# Sheet1.net
KiCad netlist of a schematic drawn in Altium Designer
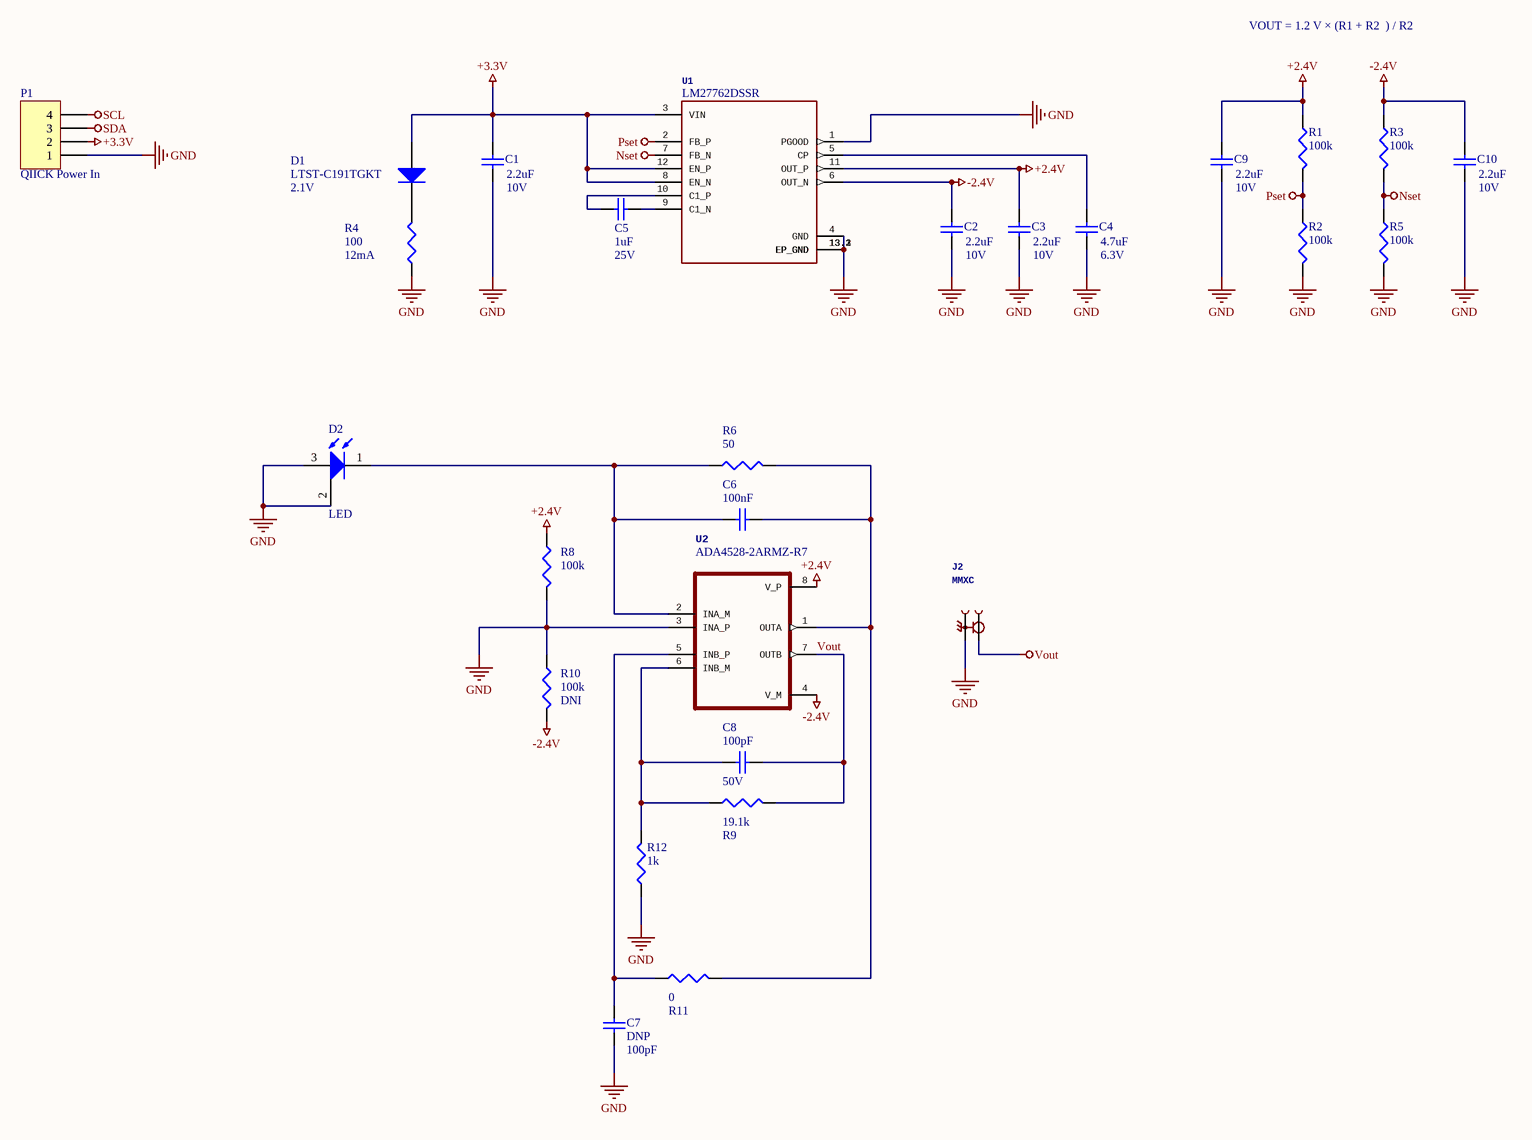
[diagram p0: Sheet1.SchDoc]

(export (version "E")
  (design (tool "Eeschema 10.0.6"))
  (components
    (comp (ref "C1")
      (value "10V")
      (footprint "0402")
      (description "2.2 µF ±20% 16V Ceramic Capacitor X6S 0402 (1005 Metric)")
      (fields (field (name "ALTIUM_VALUE") "2.2uF") (field (name "MANUFACTURER PART #") "CC0402MRX6S7BB225"))
      (libsource (lib "Miscellaneous Devices") (part "Cap"))
    )
    (comp (ref "C2")
      (value "10V")
      (footprint "0402")
      (description "2.2 µF ±20% 16V Ceramic Capacitor X6S 0402 (1005 Metric)")
      (fields (field (name "ALTIUM_VALUE") "2.2uF") (field (name "MANUFACTURER PART #") "CC0402MRX6S7BB225"))
      (libsource (lib "Miscellaneous Devices") (part "Cap"))
    )
    (comp (ref "C3")
      (value "10V")
      (footprint "0402")
      (description "2.2 µF ±20% 16V Ceramic Capacitor X6S 0402 (1005 Metric)")
      (fields (field (name "ALTIUM_VALUE") "2.2uF") (field (name "MANUFACTURER PART #") "CC0402MRX6S7BB225"))
      (libsource (lib "Miscellaneous Devices") (part "Cap"))
    )
    (comp (ref "C4")
      (value "6.3V")
      (footprint "0402")
      (description "4.7 µF ±20% 6.3V Ceramic Capacitor X6S 0402 (1005 Metric)")
      (fields (field (name "ALTIUM_VALUE") "4.7uF") (field (name "MANUFACTURER PART #") "CC0402MRX6S5BB475"))
      (libsource (lib "Miscellaneous Devices") (part "Cap"))
    )
    (comp (ref "C5")
      (value "25V")
      (footprint "0402")
      (description "1 µF ±10% 25V Ceramic Capacitor X5R 0402 (1005 Metric)")
      (fields (field (name "ALTIUM_VALUE") "1uF") (field (name "MANUFACTURER PART #") "CC0402KPX5R8BB105"))
      (libsource (lib "Miscellaneous Devices") (part "Cap"))
    )
    (comp (ref "C6")
      (value "100nF")
      (footprint "1608[0603]")
      (description "0.1 µF -20%, +80% 50V Ceramic Capacitor Y5V (F) 0603 (1608 Metric)")
      (fields (field (name "MANUFACTURER") "YAGEO") (field (name "MANUFACTURER PART #") "CC0603ZPY5V9BB104"))
      (libsource (lib "Miscellaneous Devices") (part "Cap Semi"))
    )
    (comp (ref "C7")
      (value "DNP")
      (footprint "J1-0603")
      (description "Capacitor (Semiconductor SIM Model)")
      (fields (field (name "ALTIUM_VALUE") "100pF"))
      (libsource (lib "Miscellaneous Devices") (part "Cap Semi"))
    )
    (comp (ref "C8")
      (value "50V")
      (footprint "1608[0603]")
      (description "100 pF ±5% 50V Ceramic Capacitor C0G, NP0 0603 (1608 Metric)")
      (fields
        (field (name "ALTIUM_VALUE") "100pF")
        (field (name "MANUFACTURER") "YAGEO")
        (field (name "MANUFACTURER PART #") "CC0603JPNPO9BN101")
      )
      (libsource (lib "Miscellaneous Devices") (part "Cap Semi"))
    )
    (comp (ref "C9")
      (value "10V")
      (footprint "0402")
      (description "2.2 µF ±20% 16V Ceramic Capacitor X6S 0402 (1005 Metric)")
      (fields (field (name "ALTIUM_VALUE") "2.2uF") (field (name "MANUFACTURER PART #") "CC0402MRX6S7BB225"))
      (libsource (lib "Miscellaneous Devices") (part "Cap"))
    )
    (comp (ref "C10")
      (value "10V")
      (footprint "0402")
      (description "2.2 µF ±20% 16V Ceramic Capacitor X6S 0402 (1005 Metric)")
      (fields (field (name "ALTIUM_VALUE") "2.2uF") (field (name "MANUFACTURER PART #") "CC0402MRX6S7BB225"))
      (libsource (lib "Miscellaneous Devices") (part "Cap"))
    )
    (comp (ref "D1")
      (value "LTST-C191TGKT")
      (footprint "1608[0603]")
      (description "Green 525nm LED Indication - Discrete 3.2V 0603 (1608 Metric)")
      (fields (field (name "VOLTAGE") "2.1V") (field (name "MANUFACTURER") "Lite-On Inc."))
      (libsource (lib "Miscellaneous Devices") (part "Diode"))
    )
    (comp (ref "D2") (value "LED") (footprint "FD05D") (libsource (lib "thorlabs") (part "Component_1")))
    (comp (ref "J2")
      (value "MMXC")
      (footprint "LINX_CONMMCX001-SMD")
      (description "MMCX Connector Receptacle, Female Socket 50Ohm Surface Mount Solder")
      (fields
        (field (name "MANUFACTURER") "Linx Technologies Inc.")
        (field (name "MANUFACTURER PART #") "CONMMCX001-SMD")
      )
      (libsource (lib "CONMMCX001-SMD") (part "CONMMCX001-SMD"))
    )
    (comp (ref "P1")
      (value "QIICK Power In")
      (footprint "4P vert")
      (description "Header, 4-PinConnector Header Surface Mount 4 position 0.039\" (1.00mm)")
      (fields
        (field (name "MANUFACTURER") "JST Sales America Inc.")
        (field (name "MANUFACTURER PART #") "BM04B-SRSS-TB(LF)(SN)")
      )
      (libsource (lib "Miscellaneous Connectors") (part "Header 4"))
    )
    (comp (ref "R1")
      (value "100k")
      (footprint "1608[0603]")
      (description "100 kOhms ±0.1% 0.1W, 1/10W Chip Resistor 0603 (1608 Metric) Thin Film")
      (fields (field (name "MANUFACTURER") "YAGEO") (field (name "MANUFACTURER PART #") "RT0603BRD07100KL"))
      (libsource (lib "Miscellaneous Devices") (part "Res3"))
    )
    (comp (ref "R2")
      (value "100k")
      (footprint "1608[0603]")
      (description "100 kOhms ±0.1% 0.1W, 1/10W Chip Resistor 0603 (1608 Metric) Thin Film")
      (fields (field (name "MANUFACTURER") "YAGEO") (field (name "MANUFACTURER PART #") "RT0603BRD07100KL"))
      (libsource (lib "Miscellaneous Devices") (part "Res3"))
    )
    (comp (ref "R3")
      (value "100k")
      (footprint "1608[0603]")
      (description "100 kOhms ±0.1% 0.1W, 1/10W Chip Resistor 0603 (1608 Metric) Thin Film")
      (fields (field (name "MANUFACTURER") "YAGEO") (field (name "MANUFACTURER PART #") "RT0603BRD07100KL"))
      (libsource (lib "Miscellaneous Devices") (part "Res3"))
    )
    (comp (ref "R4")
      (value "100")
      (footprint "1608[0603]")
      (description "100 Ohms ±0.1% 0.1W, 1/10W Chip Resistor 0603 (1608 Metric) Thin Film")
      (fields
        (field (name "CURRENT") "12mA")
        (field (name "MANUFACTURER PART #") "RT0603BRD07100RL")
        (field (name "MANUFACTURER") "YAGEO")
      )
      (libsource (lib "Miscellaneous Devices") (part "Res3"))
    )
    (comp (ref "R5")
      (value "100k")
      (footprint "1608[0603]")
      (description "100 kOhms ±0.1% 0.1W, 1/10W Chip Resistor 0603 (1608 Metric) Thin Film")
      (fields (field (name "MANUFACTURER") "YAGEO") (field (name "MANUFACTURER PART #") "RT0603BRD07100KL"))
      (libsource (lib "Miscellaneous Devices") (part "Res3"))
    )
    (comp (ref "R6")
      (value "50")
      (footprint "1608[0603]")
      (description "50 Ohms ±0.1% 0.1W, 1/10W Chip Resistor 0603 (1608 Metric) Thin Film")
      (fields (field (name "MANUFACTURER") "YAGEO") (field (name "MANUFACTURER PART #") "RT0603BRE0750RL"))
      (libsource (lib "Miscellaneous Devices") (part "Res3"))
    )
    (comp (ref "R8")
      (value "100k")
      (footprint "1608[0603]")
      (description "Resistor")
      (fields (field (name "Comment") "DNI"))
      (libsource (lib "Miscellaneous Devices") (part "Res3"))
    )
    (comp (ref "R9")
      (value "19.1k")
      (footprint "J1-0603")
      (description "19.1 kOhms ±0.1% 0.1W, 1/10W Chip Resistor 0603 (1608 Metric) Thin Film")
      (fields (field (name "MANUFACTURER") "YAGEO") (field (name "MANUFACTURER PART #") "RT0603BRD0719K1L"))
      (libsource (lib "Miscellaneous Devices") (part "Res3"))
    )
    (comp (ref "R10")
      (value "DNI")
      (footprint "1608[0603]")
      (description "Resistor")
      (fields (field (name "ALTIUM_VALUE") "100k"))
      (libsource (lib "Miscellaneous Devices") (part "Res3"))
    )
    (comp (ref "R11")
      (value "0")
      (footprint "J1-0603")
      (description "0 Ohms Jumper Chip Resistor 0402 (1005 Metric) Moisture Resistant Thick Film")
      (fields (field (name "MANUFACTURER") "YAGEO") (field (name "MANUFACTURER PART #") "RC0402FR-070RL"))
      (libsource (lib "Miscellaneous Devices") (part "Res3"))
    )
    (comp (ref "R12")
      (value "1k")
      (footprint "J1-0603")
      (description "1 kOhms ±0.1% 0.1W, 1/10W Chip Resistor 0603 (1608 Metric) Thin Film")
      (fields (field (name "MANUFACTURER") "YAGEO") (field (name "MANUFACTURER PART #") "RT0603BRD071KL"))
      (libsource (lib "Miscellaneous Devices") (part "Res3"))
    )
    (comp (ref "U1")
      (value "Low-Noise Positive- and Negative-Output Charge Pump With Integrated LDO 12-WSON -40 to 85")
      (footprint "VREG_LM27762DSSR")
      (fields
        (field (name "MANUFACTURER") "Texas Instruments")
        (field (name "MANUFACTURER PART #") "LM27762DSSR")
      )
      (libsource (lib "LM27762DSSR") (part "LM27762DSSR"))
    )
    (comp (ref "U2")
      (value "Op Amp Dual GP R-R I/O ±2.75V/5.5V 8-Pin MSOP T/R Check availability")
      (footprint "SOP65P490X110-8N")
      (description "Zero-Drift Amplifier 2 Circuit Rail-to-Rail 8-MSOP")
      (fields
        (field (name "MANUFACTURER") "Analog Devices")
        (field (name "MANUFACTURER PART #") "ADA4528-2ARMZ-R7")
      )
      (libsource (lib "ADA4528-2ARMZ-R7") (part "ADA4528-2ARMZ-R7"))
    )
  )
  (nets
    (net (code "1") (name "+2.4V") (class "Default")
      (node (ref "C3") (pin "2") (pinfunction "2_2") (pintype "passive"))
      (node (ref "C9") (pin "2") (pinfunction "2_2") (pintype "passive"))
      (node (ref "R1") (pin "1") (pinfunction "1_1") (pintype "passive"))
      (node (ref "R8") (pin "1") (pinfunction "1_1") (pintype "passive"))
      (node (ref "U1") (pin "11") (pinfunction "OUT_P_11") (pintype "output"))
      (node (ref "U2") (pin "8") (pinfunction "V_P_8") (pintype "power_in"))
    )
    (net (code "2") (name "+3.3V") (class "Default")
      (node (ref "C1") (pin "2") (pinfunction "2_2") (pintype "passive"))
      (node (ref "D1") (pin "1") (pinfunction "A_1") (pintype "passive"))
      (node (ref "P1") (pin "2") (pinfunction "2_2") (pintype "passive"))
      (node (ref "U1") (pin "12") (pinfunction "EN_P_12") (pintype "passive"))
      (node (ref "U1") (pin "3") (pinfunction "VIN_3") (pintype "passive"))
      (node (ref "U1") (pin "8") (pinfunction "EN_N_8") (pintype "passive"))
    )
    (net (code "3") (name "-2.4V") (class "Default")
      (node (ref "C10") (pin "2") (pinfunction "2_2") (pintype "passive"))
      (node (ref "C2") (pin "2") (pinfunction "2_2") (pintype "passive"))
      (node (ref "R10") (pin "2") (pinfunction "2_2") (pintype "passive"))
      (node (ref "R3") (pin "1") (pinfunction "1_1") (pintype "passive"))
      (node (ref "U1") (pin "6") (pinfunction "OUT_N_6") (pintype "output"))
      (node (ref "U2") (pin "4") (pinfunction "V_M_4") (pintype "power_in"))
    )
    (net (code "4") (name "GND") (class "Default")
      (node (ref "C1") (pin "1") (pinfunction "1_1") (pintype "passive"))
      (node (ref "C10") (pin "1") (pinfunction "1_1") (pintype "passive"))
      (node (ref "C2") (pin "1") (pinfunction "1_1") (pintype "passive"))
      (node (ref "C3") (pin "1") (pinfunction "1_1") (pintype "passive"))
      (node (ref "C4") (pin "1") (pinfunction "1_1") (pintype "passive"))
      (node (ref "C7") (pin "1") (pinfunction "1_1") (pintype "passive"))
      (node (ref "C9") (pin "1") (pinfunction "1_1") (pintype "passive"))
      (node (ref "D2") (pin "2") (pintype "passive"))
      (node (ref "D2") (pin "3") (pinfunction "A_3") (pintype "passive"))
      (node (ref "J2") (pin "2") (pinfunction "2_2") (pintype "passive"))
      (node (ref "P1") (pin "1") (pinfunction "1_1") (pintype "passive"))
      (node (ref "R10") (pin "1") (pinfunction "1_1") (pintype "passive"))
      (node (ref "R12") (pin "1") (pinfunction "1_1") (pintype "passive"))
      (node (ref "R2") (pin "2") (pinfunction "2_2") (pintype "passive"))
      (node (ref "R4") (pin "1") (pinfunction "1_1") (pintype "passive"))
      (node (ref "R5") (pin "2") (pinfunction "2_2") (pintype "passive"))
      (node (ref "R8") (pin "2") (pinfunction "2_2") (pintype "passive"))
      (node (ref "U1") (pin "1") (pinfunction "PGOOD_1") (pintype "output"))
      (node (ref "U1") (pin "13") (pinfunction "EP_GND_13") (pintype "power_in"))
      (node (ref "U1") (pin "13.1") (pinfunction "EP_GND_13.1") (pintype "power_in"))
      (node (ref "U1") (pin "13.2") (pinfunction "EP_GND_13.2") (pintype "power_in"))
      (node (ref "U1") (pin "13.3") (pinfunction "EP_GND_13.3") (pintype "power_in"))
      (node (ref "U1") (pin "4") (pinfunction "GND_4") (pintype "power_in"))
      (node (ref "U2") (pin "3") (pinfunction "INA_P_3") (pintype "passive"))
    )
    (net (code "5") (name "Net-(D1-K)") (class "Default")
      (node (ref "D1") (pin "2") (pinfunction "K_2") (pintype "passive"))
      (node (ref "R4") (pin "2") (pinfunction "2_2") (pintype "passive"))
    )
    (net (code "6") (name "Net-(D2-C)") (class "Default")
      (node (ref "C6") (pin "1") (pinfunction "1_1") (pintype "passive"))
      (node (ref "D2") (pin "1") (pinfunction "C_1") (pintype "passive"))
      (node (ref "R6") (pin "1") (pinfunction "1_1") (pintype "passive"))
      (node (ref "U2") (pin "2") (pinfunction "INA_M_2") (pintype "passive"))
    )
    (net (code "7") (name "Net-(U1-C1_N)") (class "Default")
      (node (ref "C5") (pin "1") (pinfunction "1_1") (pintype "passive"))
      (node (ref "U1") (pin "9") (pinfunction "C1_N_9") (pintype "passive"))
    )
    (net (code "8") (name "Net-(U1-C1_P)") (class "Default")
      (node (ref "C5") (pin "2") (pinfunction "2_2") (pintype "passive"))
      (node (ref "U1") (pin "10") (pinfunction "C1_P_10") (pintype "passive"))
    )
    (net (code "9") (name "Net-(U1-CP)") (class "Default")
      (node (ref "C4") (pin "2") (pinfunction "2_2") (pintype "passive"))
      (node (ref "U1") (pin "5") (pinfunction "CP_5") (pintype "output"))
    )
    (net (code "10") (name "Net-(U2-INB_M)") (class "Default")
      (node (ref "C8") (pin "1") (pinfunction "1_1") (pintype "passive"))
      (node (ref "R12") (pin "2") (pinfunction "2_2") (pintype "passive"))
      (node (ref "R9") (pin "1") (pinfunction "1_1") (pintype "passive"))
      (node (ref "U2") (pin "6") (pinfunction "INB_M_6") (pintype "passive"))
    )
    (net (code "11") (name "Net-(U2-INB_P)") (class "Default")
      (node (ref "C7") (pin "2") (pinfunction "2_2") (pintype "passive"))
      (node (ref "R11") (pin "1") (pinfunction "1_1") (pintype "passive"))
      (node (ref "U2") (pin "5") (pinfunction "INB_P_5") (pintype "passive"))
    )
    (net (code "12") (name "Net-(U2-OUTA)") (class "Default")
      (node (ref "C6") (pin "2") (pinfunction "2_2") (pintype "passive"))
      (node (ref "R11") (pin "2") (pinfunction "2_2") (pintype "passive"))
      (node (ref "R6") (pin "2") (pinfunction "2_2") (pintype "passive"))
      (node (ref "U2") (pin "1") (pinfunction "OUTA_1") (pintype "output"))
    )
    (net (code "13") (name "Nset") (class "Default")
      (node (ref "R3") (pin "2") (pinfunction "2_2") (pintype "passive"))
      (node (ref "R5") (pin "1") (pinfunction "1_1") (pintype "passive"))
      (node (ref "U1") (pin "7") (pinfunction "FB_N_7") (pintype "passive"))
    )
    (net (code "14") (name "Pset") (class "Default")
      (node (ref "R1") (pin "2") (pinfunction "2_2") (pintype "passive"))
      (node (ref "R2") (pin "1") (pinfunction "1_1") (pintype "passive"))
      (node (ref "U1") (pin "2") (pinfunction "FB_P_2") (pintype "passive"))
    )
    (net (code "15") (name "SCL") (class "Default")
      (node (ref "P1") (pin "4") (pinfunction "4_4") (pintype "passive"))
    )
    (net (code "16") (name "SDA") (class "Default")
      (node (ref "P1") (pin "3") (pinfunction "3_3") (pintype "passive"))
    )
    (net (code "17") (name "Vout") (class "Default")
      (node (ref "C8") (pin "2") (pinfunction "2_2") (pintype "passive"))
      (node (ref "J2") (pin "1") (pinfunction "1_1") (pintype "passive"))
      (node (ref "R9") (pin "2") (pinfunction "2_2") (pintype "passive"))
      (node (ref "U2") (pin "7") (pinfunction "OUTB_7") (pintype "output"))
    )
  )
)
